# 03_-_MAIN_BOARD.net
KiCad netlist of a schematic drawn in Altium Designer
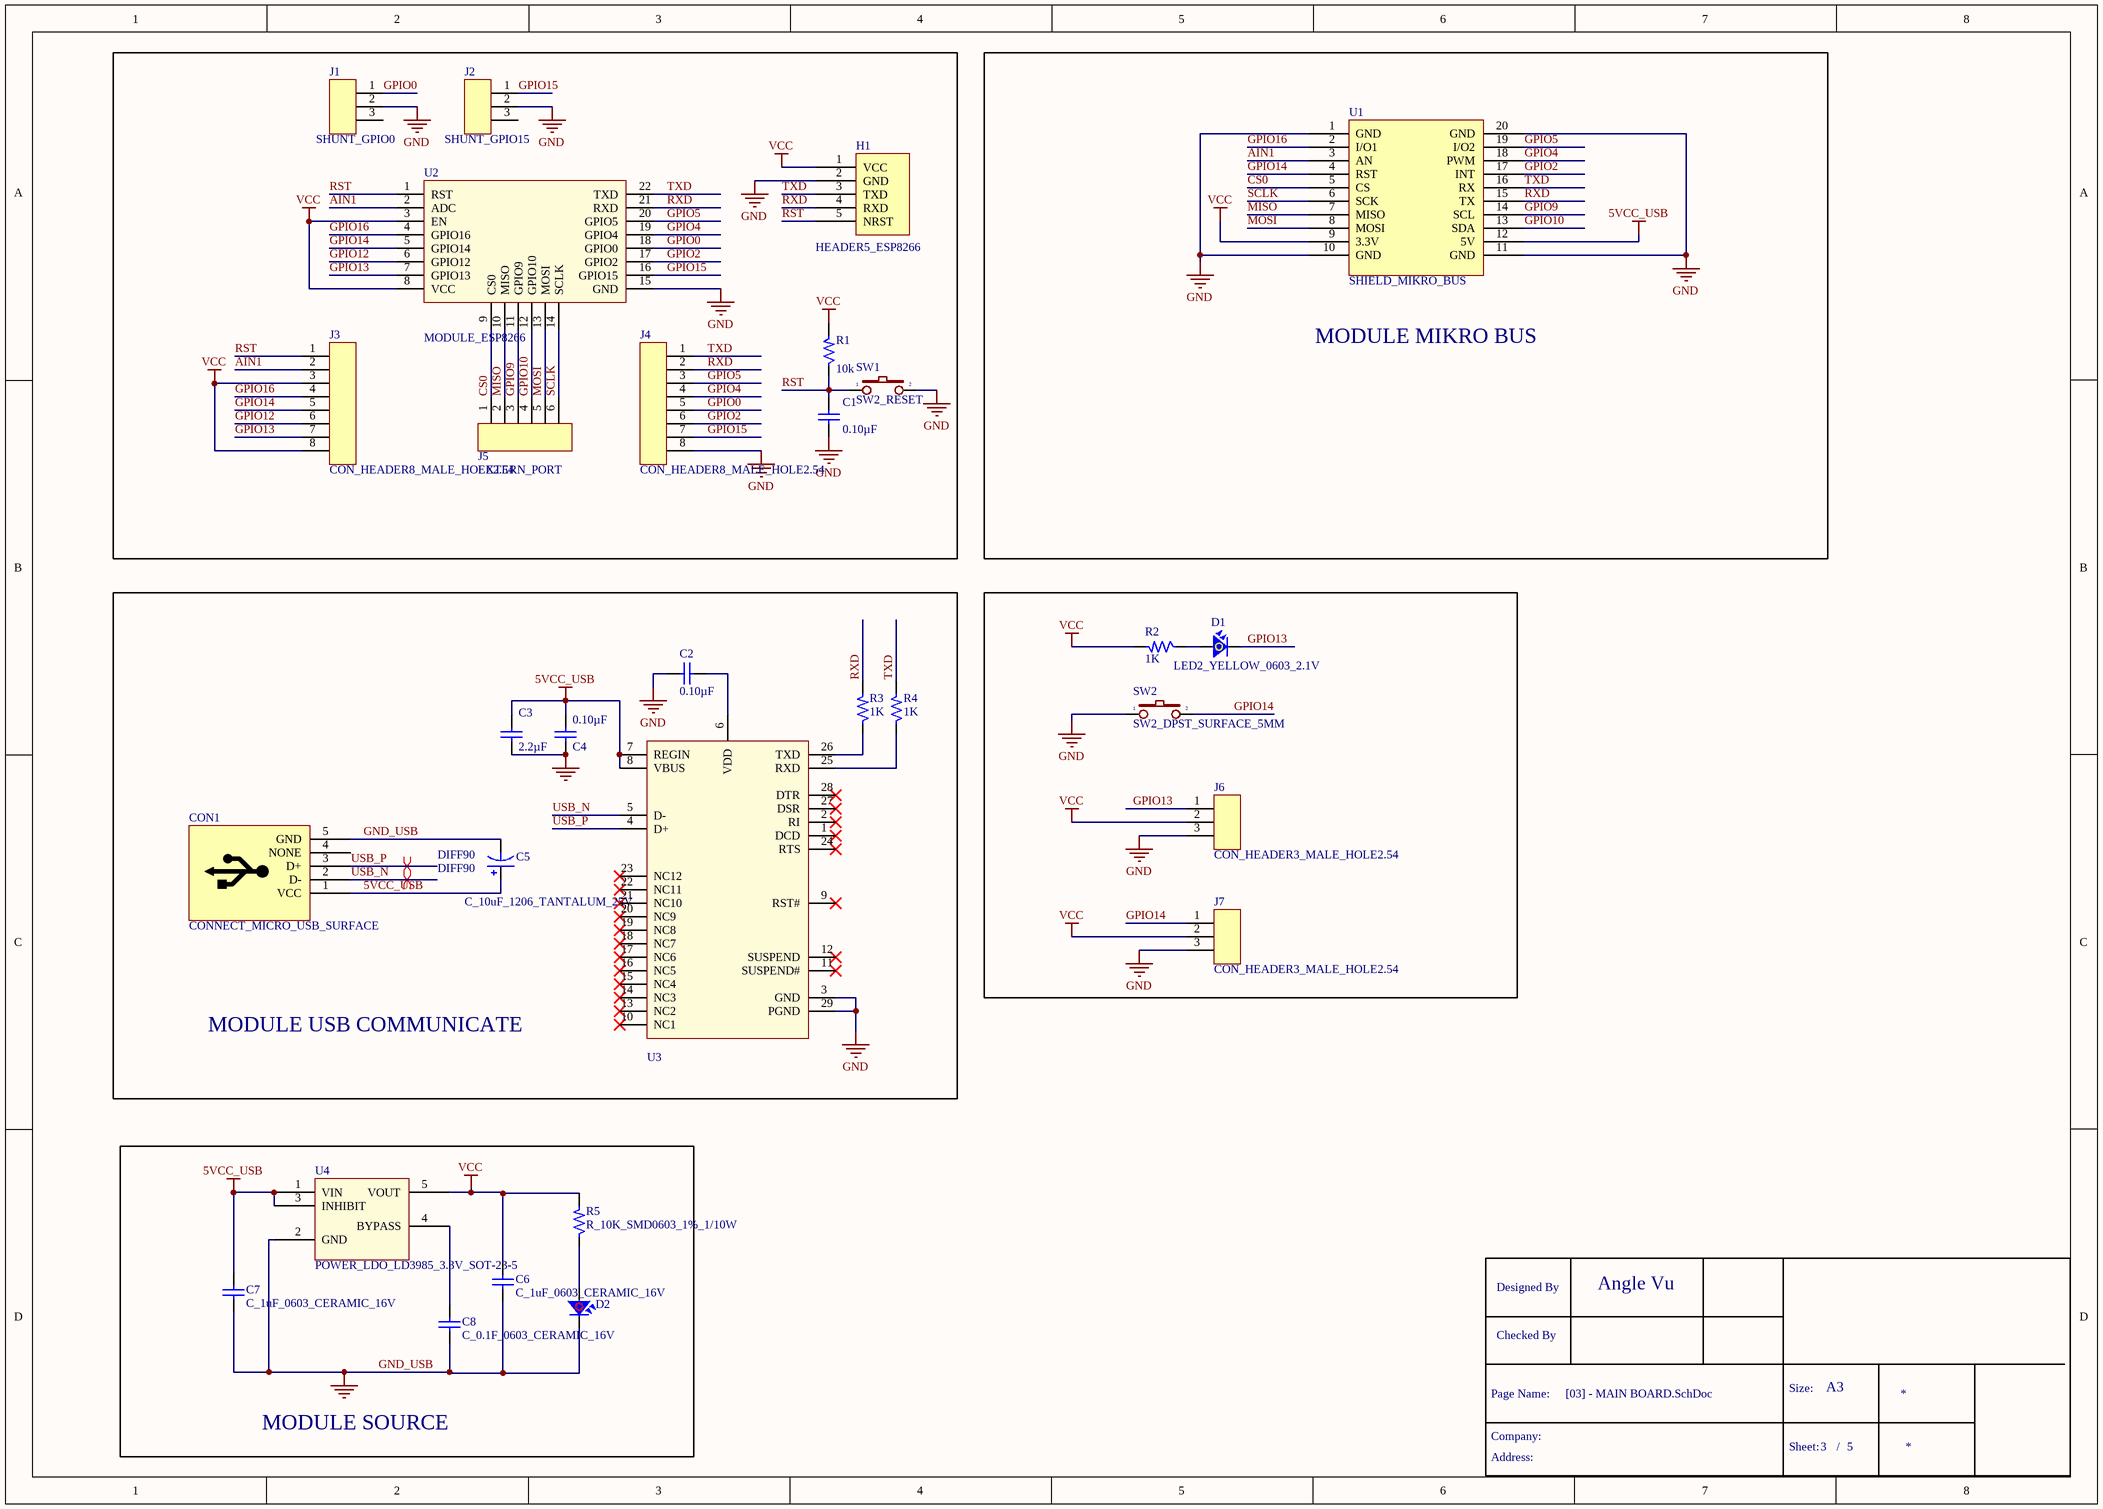
[diagram p0: [03] - MAIN BOARD.SchDoc]

(export (version "E")
  (design (tool "Eeschema 10.0.6"))
  (components
    (comp (ref "C1")
      (value "C_0.1F_0603_CERAMIC_16V")
      (footprint "CAP_SMD0603")
      (description "CAP CER 0.1UF 16V X7R 0603")
      (fields
        (field (name "MANUFACTURER") "Murata Electronics North America")
        (field (name "MANUFACTURER PART NUMBER") "GRM188R71C104KA01D")
        (field (name "CAPACITANCE") "0.10µF")
      )
      (libsource (lib "LIB_ALTIUM") (part "C_0.1F_0603_CERAMIC_16V"))
    )
    (comp (ref "C2")
      (value "C_0.1F_0603_CERAMIC_16V")
      (footprint "CAP_SMD0603")
      (description "CAP CER 0.1UF 16V X7R 0603")
      (fields
        (field (name "MANUFACTURER") "Murata Electronics North America")
        (field (name "MANUFACTURER PART NUMBER") "GRM188R71C104KA01D")
        (field (name "CAPACITANCE") "0.10µF")
      )
      (libsource (lib "LIB_ALTIUM") (part "C_0.1F_0603_CERAMIC_16V"))
    )
    (comp (ref "C3")
      (value "C_2.2uF_0603_CERAMIC_16V")
      (footprint "CAP_SMD0603")
      (description "CAP CER 2.2UF 16V X5R 0603")
      (fields
        (field (name "MANUFACTURER") "Murata Electronics North America")
        (field (name "MANUFACTURER PART NUMBER") "GRM188R61C225KE15D")
        (field (name "CAPACITANCE") "2.2µF")
      )
      (libsource (lib "LIB_ALTIUM") (part "C_2.2uF_0603_CERAMIC_16V"))
    )
    (comp (ref "C4")
      (value "C_0.1F_0603_CERAMIC_16V")
      (footprint "CAP_SMD0603")
      (description "CAP CER 0.1UF 16V X7R 0603")
      (fields
        (field (name "MANUFACTURER") "Murata Electronics North America")
        (field (name "MANUFACTURER PART NUMBER") "GRM188R71C104KA01D")
        (field (name "CAPACITANCE") "0.10µF")
      )
      (libsource (lib "LIB_ALTIUM") (part "C_0.1F_0603_CERAMIC_16V"))
    )
    (comp (ref "C5")
      (value "C_10uF_1206_TANTALUM_25V")
      (footprint "CAP_SMD1206_TANTALUM")
      (description "CAP TANT 10UF 25V 10% 1206")
      (fields
        (field (name "MANUFACTURER") "AVX Corporation")
        (field (name "MANUFACTURER PART NUMBER") "F951E106KAAAQ2")
      )
      (libsource (lib "LIB_ALTIUM") (part "C_10uF_1206_TANTALUM_25V"))
    )
    (comp (ref "C6")
      (value "C_1uF_0603_CERAMIC_16V")
      (footprint "CAP_SMD0603")
      (description "CAP CER 1UF 16V X5R 0603")
      (fields
        (field (name "MANUFACTURER") "Murata Electronics North America")
        (field (name "MANUFACTURER PART NUMBER") "GRM188R61C105KA93D")
      )
      (libsource (lib "LIB_ALTIUM") (part "C_1uF_0603_CERAMIC_16V"))
    )
    (comp (ref "C7")
      (value "C_1uF_0603_CERAMIC_16V")
      (footprint "CAP_SMD0603")
      (description "CAP CER 1UF 16V X5R 0603")
      (fields
        (field (name "MANUFACTURER") "Murata Electronics North America")
        (field (name "MANUFACTURER PART NUMBER") "GRM188R61C105KA93D")
      )
      (libsource (lib "LIB_ALTIUM") (part "C_1uF_0603_CERAMIC_16V"))
    )
    (comp (ref "C8")
      (value "C_0.1F_0603_CERAMIC_16V")
      (footprint "CAP_SMD0603")
      (description "CAP CER 0.1UF 16V X7R 0603")
      (fields
        (field (name "MANUFACTURER") "Murata Electronics North America")
        (field (name "MANUFACTURER PART NUMBER") "GRM188R71C104KA01D")
      )
      (libsource (lib "LIB_ALTIUM") (part "C_0.1F_0603_CERAMIC_16V"))
    )
    (comp (ref "CON1")
      (value "CONNECT_MICRO_USB_SURFACE")
      (footprint "CON_MICRO_USB_HOLE")
      (description "CONN RCPT STD MICRO USB TYPE B")
      (fields
        (field (name "MANUFACTURER") "Amphenol FCI")
        (field (name "MANUFACTURER PART NUMBER") "10103593-0001LF")
      )
      (libsource (lib "LIB_ALTIUM") (part "CONNECT_MICRO_USB_SURFACE"))
    )
    (comp (ref "D1")
      (value "LED2_YELLOW_0603_2.1V")
      (footprint "LED_YELLOW_SMD0603")
      (description "LED YELLOW CLEAR 0603 SMD")
      (fields
        (field (name "MANUFACTURER") "Lite-On Inc.")
        (field (name "MANUFACTURER PART NUMBER") "LTST-C191KSKT")
      )
      (libsource (lib "LIB_ALTIUM") (part "LED2_YELLOW_0603_2.1V"))
    )
    (comp (ref "D2")
      (value "LED2_RED_0603_2V")
      (footprint "LED_RED_SMD0603")
      (description "LED RED CLEAR 0603 SMD")
      (fields
        (field (name "MANUFACTURER") "Lite-On Inc.")
        (field (name "MANUFACTURER PART NUMBER") "LTST-C191KRKT")
      )
      (libsource (lib "LIB_ALTIUM") (part "LED2_RED_0603_2V"))
    )
    (comp (ref "H1")
      (value "HEADER5_ESP8266")
      (footprint "HEADER5_ESP8266_HOLE_2.54")
      (description "CONN HEADER 5 POS 2.54")
      (fields
        (field (name "MANUFACTURER") "Wurth Electronics Inc")
        (field (name "MANUFACTURER PART NUMBER") "61300511121")
      )
      (libsource (lib "LIB_ALTIUM") (part "HEADER5_ESP8266_HOLE_2.54"))
    )
    (comp (ref "J1")
      (value "SHUNT_GPIO0")
      (footprint "CON_HEADER3_HOLE_2.54")
      (description "CON_HEADER10_HOLE2.54")
      (fields (field (name "MANUFACTURER") "3M") (field (name "MANUFACTURER PART NUMBER") "961102-6404-AR"))
      (libsource (lib "") (part "CON_HEADER3_MALE_HOLE2.54_1"))
    )
    (comp (ref "J2")
      (value "SHUNT_GPIO15")
      (footprint "CON_HEADER3_HOLE_2.54")
      (description "CON_HEADER10_HOLE2.54")
      (fields (field (name "MANUFACTURER") "3M") (field (name "MANUFACTURER PART NUMBER") "961102-6404-AR"))
      (libsource (lib "") (part "CON_HEADER3_MALE_HOLE2.54_1"))
    )
    (comp (ref "J3")
      (value "CON_HEADER8_MALE_HOLE2.54")
      (footprint "CON_HEADER8_HOLE_2.54")
      (description "CON_HEADER10_HOLE2.54")
      (fields (field (name "MANUFACTURER") "3M") (field (name "MANUFACTURER PART NUMBER") "961102-6404-AR"))
      (libsource (lib "LIB_ALTIUM") (part "CON_HEADER8_MALE_HOLE2.54"))
    )
    (comp (ref "J4")
      (value "CON_HEADER8_MALE_HOLE2.54")
      (footprint "CON_HEADER8_HOLE_2.54")
      (description "CON_HEADER10_HOLE2.54")
      (fields (field (name "MANUFACTURER") "3M") (field (name "MANUFACTURER PART NUMBER") "961102-6404-AR"))
      (libsource (lib "") (part "CON_HEADER8_MALE_HOLE2.54_1"))
    )
    (comp (ref "J5")
      (value "EXTERN_PORT")
      (footprint "CON_HEADER6_HOLE_2.54")
      (description "CON_HEADER10_HOLE2.54")
      (fields (field (name "MANUFACTURER") "3M") (field (name "MANUFACTURER PART NUMBER") "961102-6404-AR"))
      (libsource (lib "LIB_ALTIUM") (part "CON_HEADER6_MALE_HOLE2.54"))
    )
    (comp (ref "J6")
      (value "CON_HEADER3_MALE_HOLE2.54")
      (footprint "CON_HEADER3_HOLE_2.54")
      (description "CON_HEADER10_HOLE2.54")
      (fields (field (name "MANUFACTURER") "3M") (field (name "MANUFACTURER PART NUMBER") "961102-6404-AR"))
      (libsource (lib "LIB_ALTIUM") (part "CON_HEADER3_MALE_HOLE2.54"))
    )
    (comp (ref "J7")
      (value "CON_HEADER3_MALE_HOLE2.54")
      (footprint "CON_HEADER3_HOLE_2.54")
      (description "CON_HEADER10_HOLE2.54")
      (fields (field (name "MANUFACTURER") "3M") (field (name "MANUFACTURER PART NUMBER") "961102-6404-AR"))
      (libsource (lib "LIB_ALTIUM") (part "CON_HEADER3_MALE_HOLE2.54"))
    )
    (comp (ref "R1")
      (value "R_10K_SMD0603_1%_1/10W")
      (footprint "RES_SMD0603")
      (description "RES SMD 10K OHM 1% 1/10W 0603")
      (fields
        (field (name "MANUFACTURER") "Yageo")
        (field (name "MANUFACTURER PART NUMBER") "RC0603FR-0710KL")
        (field (name "RESISTANCE (OHMS)") "10k")
      )
      (libsource (lib "LIB_ALTIUM") (part "R_10K_SMD0603_1%_1/10W"))
    )
    (comp (ref "R2")
      (value "R_1K2_SMD0603_1%_1/10W")
      (footprint "RES_SMD0603")
      (description "RES SMD 1.2K OHM 1% 1/10W 0603")
      (fields
        (field (name "MANUFACTURER") "Yageo")
        (field (name "MANUFACTURER PART NUMBER") "RC0603FR-071K2L")
        (field (name "RESISTANCE (OHMS)") "1K")
      )
      (libsource (lib "LIB_ALTIUM") (part "R_1K2_SMD0603_1%_1/10W"))
    )
    (comp (ref "R3")
      (value "R_1K2_SMD0603_1%_1/10W")
      (footprint "RES_SMD0603")
      (description "RES SMD 1.2K OHM 1% 1/10W 0603")
      (fields
        (field (name "MANUFACTURER") "Yageo")
        (field (name "MANUFACTURER PART NUMBER") "RC0603FR-071K2L")
        (field (name "RESISTANCE (OHMS)") "1K")
      )
      (libsource (lib "LIB_ALTIUM") (part "R_1K2_SMD0603_1%_1/10W"))
    )
    (comp (ref "R4")
      (value "R_1K2_SMD0603_1%_1/10W")
      (footprint "RES_SMD0603")
      (description "RES SMD 1.2K OHM 1% 1/10W 0603")
      (fields
        (field (name "MANUFACTURER") "Yageo")
        (field (name "MANUFACTURER PART NUMBER") "RC0603FR-071K2L")
        (field (name "RESISTANCE (OHMS)") "1K")
      )
      (libsource (lib "LIB_ALTIUM") (part "R_1K2_SMD0603_1%_1/10W"))
    )
    (comp (ref "R5")
      (value "R_10K_SMD0603_1%_1/10W")
      (footprint "RES_SMD0603")
      (description "RES SMD 10K OHM 1% 1/10W 0603")
      (fields
        (field (name "MANUFACTURER") "Yageo")
        (field (name "MANUFACTURER PART NUMBER") "RC0603FR-0710KL")
      )
      (libsource (lib "LIB_ALTIUM") (part "R_10K_SMD0603_1%_1/10W"))
    )
    (comp (ref "SW1")
      (value "SW2_RESET")
      (footprint "SW2-SMD")
      (description "SWITCH TACTILE SPST-NO 0.05A 12V")
      (fields
        (field (name "MANUFACTURER") "Wurth Electronics Inc")
        (field (name "MANUFACTURER PART NUMBER") "434121050836")
      )
      (libsource (lib "LIB_ALTIUM") (part "SW2_DPST_SURFACE_5MM"))
    )
    (comp (ref "SW2")
      (value "SW2_DPST_SURFACE_5MM")
      (footprint "SW2-SMD")
      (description "SWITCH TACTILE SPST-NO 0.05A 12V")
      (fields
        (field (name "MANUFACTURER") "Wurth Electronics Inc")
        (field (name "MANUFACTURER PART NUMBER") "434121050836")
      )
      (libsource (lib "LIB_ALTIUM") (part "SW2_DPST_SURFACE_5MM"))
    )
    (comp (ref "U1")
      (value "SHIELD_MIKRO_BUS")
      (footprint "SHIELD_MIKRO_BUS")
      (libsource (lib "SchematicLib") (part "SHIELD_MIKRO_BUS"))
    )
    (comp (ref "U2")
      (value "MODULE_ESP8266")
      (footprint "MODULE_ESP8266")
      (libsource (lib "LIB_ALTIUM") (part "MODULE_ESP8266"))
    )
    (comp (ref "U3")
      (value "USB_CP2102-GMR")
      (footprint "QFN_28PIN_USBC2102")
      (description "IC USB-TO-UART BRIDGE 28VQFN")
      (fields
        (field (name "MANUFACTURER") "Silicon Labs")
        (field (name "MANUFACTURER PART NUMBER") "CP2102-GMR")
      )
      (libsource (lib "LIB_ALTIUM") (part "USB_CP2102-GMR"))
    )
    (comp (ref "U4")
      (value "POWER_LDO_LD3985_3.3V_SOT-23-5")
      (footprint "POWER_LDO_LDR3985-3.3")
      (description "IC REG LDO 3.3V 0.15A SOT23-5")
      (fields
        (field (name "MANUFACTURER") "STMicroelectronics")
        (field (name "MANUFACTURER PART NUMBER") "LD3985M33R")
      )
      (libsource (lib "LIB_ALTIUM") (part "POWER_LDO_LD3985_3.3V_SOT-23-5"))
    )
  )
  (nets
    (net (code "1") (name "/AIN1") (class "Default")
      (node (ref "J3") (pin "2") (pinfunction "SIGN-_2") (pintype "passive"))
      (node (ref "U1") (pin "3") (pinfunction "AN_3") (pintype "passive"))
      (node (ref "U2") (pin "2") (pinfunction "ADC_2") (pintype "passive"))
    )
    (net (code "2") (name "/CS0") (class "Default")
      (node (ref "J5") (pin "1") (pinfunction "SIGN+_1") (pintype "passive"))
      (node (ref "U1") (pin "5") (pinfunction "CS_5") (pintype "passive"))
      (node (ref "U2") (pin "9") (pinfunction "CS0_9") (pintype "passive"))
    )
    (net (code "3") (name "/GPIO0") (class "Default")
      (node (ref "J1") (pin "1") (pinfunction "SIGN+_1") (pintype "passive"))
      (node (ref "J4") (pin "5") (pinfunction "5_5") (pintype "passive"))
      (node (ref "U2") (pin "18") (pinfunction "GPIO0_18") (pintype "passive"))
    )
    (net (code "4") (name "/GPIO2") (class "Default")
      (node (ref "J4") (pin "6") (pinfunction "6_6") (pintype "passive"))
      (node (ref "U1") (pin "17") (pinfunction "INT_17") (pintype "passive"))
      (node (ref "U2") (pin "17") (pinfunction "GPIO2_17") (pintype "passive"))
    )
    (net (code "5") (name "/GPIO4") (class "Default")
      (node (ref "J4") (pin "4") (pinfunction "4_4") (pintype "passive"))
      (node (ref "U1") (pin "18") (pinfunction "PWM_18") (pintype "passive"))
      (node (ref "U2") (pin "19") (pinfunction "GPIO4_19") (pintype "passive"))
    )
    (net (code "6") (name "/GPIO5") (class "Default")
      (node (ref "J4") (pin "3") (pinfunction "3_3") (pintype "passive"))
      (node (ref "U1") (pin "19") (pinfunction "I/O2_19") (pintype "passive"))
      (node (ref "U2") (pin "20") (pinfunction "GPIO5_20") (pintype "passive"))
    )
    (net (code "7") (name "/GPIO9") (class "Default")
      (node (ref "J5") (pin "3") (pinfunction "3_3") (pintype "passive"))
      (node (ref "U1") (pin "14") (pinfunction "SCL_14") (pintype "passive"))
      (node (ref "U2") (pin "11") (pinfunction "GPIO9_11") (pintype "passive"))
    )
    (net (code "8") (name "/GPIO10") (class "Default")
      (node (ref "J5") (pin "4") (pinfunction "4_4") (pintype "passive"))
      (node (ref "U1") (pin "13") (pinfunction "SDA_13") (pintype "passive"))
      (node (ref "U2") (pin "12") (pinfunction "GPIO10_12") (pintype "passive"))
    )
    (net (code "9") (name "/GPIO12") (class "Default")
      (node (ref "J3") (pin "6") (pinfunction "6_6") (pintype "passive"))
      (node (ref "U2") (pin "6") (pinfunction "GPIO12_6") (pintype "passive"))
    )
    (net (code "10") (name "/GPIO13") (class "Default")
      (node (ref "D1") (pin "2") (pinfunction "2_2") (pintype "passive"))
      (node (ref "J3") (pin "7") (pinfunction "7_7") (pintype "passive"))
      (node (ref "J6") (pin "1") (pinfunction "SIGN+_1") (pintype "passive"))
      (node (ref "U2") (pin "7") (pinfunction "GPIO13_7") (pintype "passive"))
    )
    (net (code "11") (name "/GPIO14") (class "Default")
      (node (ref "J3") (pin "5") (pinfunction "5_5") (pintype "passive"))
      (node (ref "J7") (pin "1") (pinfunction "SIGN+_1") (pintype "passive"))
      (node (ref "SW2") (pin "2") (pinfunction "2_2") (pintype "passive"))
      (node (ref "U1") (pin "4") (pinfunction "RST_4") (pintype "passive"))
      (node (ref "U2") (pin "5") (pinfunction "GPIO14_5") (pintype "passive"))
    )
    (net (code "12") (name "/GPIO15") (class "Default")
      (node (ref "J2") (pin "1") (pinfunction "SIGN+_1") (pintype "passive"))
      (node (ref "J4") (pin "7") (pinfunction "7_7") (pintype "passive"))
      (node (ref "U2") (pin "16") (pinfunction "GPIO15_16") (pintype "passive"))
    )
    (net (code "13") (name "/GPIO16") (class "Default")
      (node (ref "J3") (pin "4") (pinfunction "4_4") (pintype "passive"))
      (node (ref "U1") (pin "2") (pinfunction "I/O1_2") (pintype "passive"))
      (node (ref "U2") (pin "4") (pinfunction "GPIO16_4") (pintype "passive"))
    )
    (net (code "14") (name "/MISO") (class "Default")
      (node (ref "J5") (pin "2") (pinfunction "SIGN-_2") (pintype "passive"))
      (node (ref "U1") (pin "7") (pinfunction "MISO_7") (pintype "passive"))
      (node (ref "U2") (pin "10") (pinfunction "MISO_10") (pintype "passive"))
    )
    (net (code "15") (name "/MOSI") (class "Default")
      (node (ref "J5") (pin "5") (pinfunction "5_5") (pintype "passive"))
      (node (ref "U1") (pin "8") (pinfunction "MOSI_8") (pintype "passive"))
      (node (ref "U2") (pin "13") (pinfunction "MOSI_13") (pintype "passive"))
    )
    (net (code "16") (name "/RST") (class "Default")
      (node (ref "C1") (pin "2") (pinfunction "2_2") (pintype "passive"))
      (node (ref "H1") (pin "5") (pinfunction "NRST_5") (pintype "passive"))
      (node (ref "J3") (pin "1") (pinfunction "SIGN+_1") (pintype "passive"))
      (node (ref "R1") (pin "1") (pinfunction "1_1") (pintype "passive"))
      (node (ref "SW1") (pin "1") (pinfunction "1_1") (pintype "passive"))
      (node (ref "U2") (pin "1") (pinfunction "RST_1") (pintype "passive"))
    )
    (net (code "17") (name "/RXD") (class "Default")
      (node (ref "H1") (pin "4") (pinfunction "RXD_4") (pintype "passive"))
      (node (ref "J4") (pin "2") (pinfunction "SIGN-_2") (pintype "passive"))
      (node (ref "R3") (pin "2") (pinfunction "2_2") (pintype "passive"))
      (node (ref "U1") (pin "15") (pinfunction "TX_15") (pintype "passive"))
      (node (ref "U2") (pin "21") (pinfunction "RXD_21") (pintype "passive"))
    )
    (net (code "18") (name "/SCLK") (class "Default")
      (node (ref "J5") (pin "6") (pinfunction "6_6") (pintype "passive"))
      (node (ref "U1") (pin "6") (pinfunction "SCK_6") (pintype "passive"))
      (node (ref "U2") (pin "14") (pinfunction "SCLK_14") (pintype "passive"))
    )
    (net (code "19") (name "/TXD") (class "Default")
      (node (ref "H1") (pin "3") (pinfunction "TXD_3") (pintype "passive"))
      (node (ref "J4") (pin "1") (pinfunction "SIGN+_1") (pintype "passive"))
      (node (ref "R4") (pin "2") (pinfunction "2_2") (pintype "passive"))
      (node (ref "U1") (pin "16") (pinfunction "RX_16") (pintype "passive"))
      (node (ref "U2") (pin "22") (pinfunction "TXD_22") (pintype "passive"))
    )
    (net (code "20") (name "/USB_N") (class "Default")
      (node (ref "CON1") (pin "2") (pinfunction "D-_2") (pintype "passive"))
      (node (ref "U3") (pin "5") (pinfunction "D-_5") (pintype "passive"))
    )
    (net (code "21") (name "/USB_P") (class "Default")
      (node (ref "CON1") (pin "3") (pinfunction "D+_3") (pintype "passive"))
      (node (ref "U3") (pin "4") (pinfunction "D+_4") (pintype "passive"))
    )
    (net (code "22") (name "5VCC_USB") (class "Default")
      (node (ref "C3") (pin "2") (pinfunction "2_2") (pintype "passive"))
      (node (ref "C4") (pin "2") (pinfunction "2_2") (pintype "passive"))
      (node (ref "C5") (pin "1") (pinfunction "1_1") (pintype "passive"))
      (node (ref "C7") (pin "2") (pinfunction "2_2") (pintype "passive"))
      (node (ref "CON1") (pin "1") (pinfunction "VCC_1") (pintype "passive"))
      (node (ref "U1") (pin "12") (pinfunction "5V_12") (pintype "passive"))
      (node (ref "U3") (pin "7") (pinfunction "REGIN_7") (pintype "passive"))
      (node (ref "U3") (pin "8") (pinfunction "VBUS_8") (pintype "passive"))
      (node (ref "U4") (pin "1") (pinfunction "VIN_1") (pintype "passive"))
      (node (ref "U4") (pin "3") (pinfunction "INHIBIT_3") (pintype "passive"))
    )
    (net (code "23") (name "GND") (class "Default")
      (node (ref "C1") (pin "1") (pinfunction "1_1") (pintype "passive"))
      (node (ref "C2") (pin "2") (pinfunction "2_2") (pintype "passive"))
      (node (ref "C3") (pin "1") (pinfunction "1_1") (pintype "passive"))
      (node (ref "C4") (pin "1") (pinfunction "1_1") (pintype "passive"))
      (node (ref "C5") (pin "2") (pinfunction "2_2") (pintype "passive"))
      (node (ref "C6") (pin "1") (pinfunction "1_1") (pintype "passive"))
      (node (ref "C7") (pin "1") (pinfunction "1_1") (pintype "passive"))
      (node (ref "C8") (pin "1") (pinfunction "1_1") (pintype "passive"))
      (node (ref "CON1") (pin "5") (pinfunction "GND_5") (pintype "passive"))
      (node (ref "D2") (pin "2") (pinfunction "2_2") (pintype "passive"))
      (node (ref "H1") (pin "2") (pinfunction "GND_2") (pintype "passive"))
      (node (ref "J1") (pin "2") (pinfunction "SIGN-_2") (pintype "passive"))
      (node (ref "J2") (pin "2") (pinfunction "SIGN-_2") (pintype "passive"))
      (node (ref "J4") (pin "8") (pinfunction "8_8") (pintype "passive"))
      (node (ref "J6") (pin "3") (pinfunction "3_3") (pintype "passive"))
      (node (ref "J7") (pin "3") (pinfunction "3_3") (pintype "passive"))
      (node (ref "SW1") (pin "2") (pinfunction "2_2") (pintype "passive"))
      (node (ref "SW2") (pin "1") (pinfunction "1_1") (pintype "passive"))
      (node (ref "U1") (pin "1") (pinfunction "GND_1") (pintype "passive"))
      (node (ref "U1") (pin "10") (pinfunction "GND_10") (pintype "passive"))
      (node (ref "U1") (pin "11") (pinfunction "GND_11") (pintype "passive"))
      (node (ref "U1") (pin "20") (pinfunction "GND_20") (pintype "passive"))
      (node (ref "U2") (pin "15") (pinfunction "GND_15") (pintype "passive"))
      (node (ref "U3") (pin "29") (pinfunction "PGND_29") (pintype "passive"))
      (node (ref "U3") (pin "3") (pinfunction "GND_3") (pintype "passive"))
      (node (ref "U4") (pin "2") (pinfunction "GND_2") (pintype "passive"))
    )
    (net (code "24") (name "Net-(D1-Pad1)") (class "Default")
      (node (ref "D1") (pin "1") (pinfunction "1_1") (pintype "passive"))
      (node (ref "R2") (pin "1") (pinfunction "1_1") (pintype "passive"))
    )
    (net (code "25") (name "Net-(D2-Pad1)") (class "Default")
      (node (ref "D2") (pin "1") (pinfunction "1_1") (pintype "passive"))
      (node (ref "R5") (pin "1") (pinfunction "1_1") (pintype "passive"))
    )
    (net (code "26") (name "Net-(U3-RXD)") (class "Default")
      (node (ref "R4") (pin "1") (pinfunction "1_1") (pintype "passive"))
      (node (ref "U3") (pin "25") (pinfunction "RXD_25") (pintype "passive"))
    )
    (net (code "27") (name "Net-(U3-TXD)") (class "Default")
      (node (ref "R3") (pin "1") (pinfunction "1_1") (pintype "passive"))
      (node (ref "U3") (pin "26") (pinfunction "TXD_26") (pintype "passive"))
    )
    (net (code "28") (name "Net-(U3-VDD)") (class "Default")
      (node (ref "C2") (pin "1") (pinfunction "1_1") (pintype "passive"))
      (node (ref "U3") (pin "6") (pinfunction "VDD_6") (pintype "passive"))
    )
    (net (code "29") (name "Net-(U4-BYPASS)") (class "Default")
      (node (ref "C8") (pin "2") (pinfunction "2_2") (pintype "passive"))
      (node (ref "U4") (pin "4") (pinfunction "BYPASS_4") (pintype "passive"))
    )
    (net (code "30") (name "VCC") (class "Default")
      (node (ref "C6") (pin "2") (pinfunction "2_2") (pintype "passive"))
      (node (ref "H1") (pin "1") (pinfunction "VCC_1") (pintype "passive"))
      (node (ref "J3") (pin "3") (pinfunction "3_3") (pintype "passive"))
      (node (ref "J3") (pin "8") (pinfunction "8_8") (pintype "passive"))
      (node (ref "J6") (pin "2") (pinfunction "SIGN-_2") (pintype "passive"))
      (node (ref "J7") (pin "2") (pinfunction "SIGN-_2") (pintype "passive"))
      (node (ref "R1") (pin "2") (pinfunction "2_2") (pintype "passive"))
      (node (ref "R2") (pin "2") (pinfunction "2_2") (pintype "passive"))
      (node (ref "R5") (pin "2") (pinfunction "2_2") (pintype "passive"))
      (node (ref "U1") (pin "9") (pinfunction "3.3V_9") (pintype "passive"))
      (node (ref "U2") (pin "3") (pinfunction "EN_3") (pintype "passive"))
      (node (ref "U2") (pin "8") (pinfunction "VCC_8") (pintype "passive"))
      (node (ref "U4") (pin "5") (pinfunction "VOUT_5") (pintype "passive"))
    )
    (net (code "31") (name "unconnected-(CON1-NONE-Pad4)") (class "Default")
      (node (ref "CON1") (pin "4") (pinfunction "NONE_4") (pintype "passive"))
    )
    (net (code "32") (name "unconnected-(J1-Pad3)") (class "Default")
      (node (ref "J1") (pin "3") (pinfunction "3_3") (pintype "passive"))
    )
    (net (code "33") (name "unconnected-(J2-Pad3)") (class "Default")
      (node (ref "J2") (pin "3") (pinfunction "3_3") (pintype "passive"))
    )
    (net (code "34") (name "unconnected-(U3-DCD-Pad1)") (class "Default")
      (node (ref "U3") (pin "1") (pinfunction "DCD_1") (pintype "passive+no_connect"))
    )
    (net (code "35") (name "unconnected-(U3-DSR-Pad27)") (class "Default")
      (node (ref "U3") (pin "27") (pinfunction "DSR_27") (pintype "passive+no_connect"))
    )
    (net (code "36") (name "unconnected-(U3-DTR-Pad28)") (class "Default")
      (node (ref "U3") (pin "28") (pinfunction "DTR_28") (pintype "passive+no_connect"))
    )
    (net (code "37") (name "unconnected-(U3-NC1-Pad10)") (class "Default")
      (node (ref "U3") (pin "10") (pinfunction "NC1_10") (pintype "passive+no_connect"))
    )
    (net (code "38") (name "unconnected-(U3-NC2-Pad13)") (class "Default")
      (node (ref "U3") (pin "13") (pinfunction "NC2_13") (pintype "passive+no_connect"))
    )
    (net (code "39") (name "unconnected-(U3-NC3-Pad14)") (class "Default")
      (node (ref "U3") (pin "14") (pinfunction "NC3_14") (pintype "passive+no_connect"))
    )
    (net (code "40") (name "unconnected-(U3-NC4-Pad15)") (class "Default")
      (node (ref "U3") (pin "15") (pinfunction "NC4_15") (pintype "passive+no_connect"))
    )
    (net (code "41") (name "unconnected-(U3-NC5-Pad16)") (class "Default")
      (node (ref "U3") (pin "16") (pinfunction "NC5_16") (pintype "passive+no_connect"))
    )
    (net (code "42") (name "unconnected-(U3-NC6-Pad17)") (class "Default")
      (node (ref "U3") (pin "17") (pinfunction "NC6_17") (pintype "passive+no_connect"))
    )
    (net (code "43") (name "unconnected-(U3-NC7-Pad18)") (class "Default")
      (node (ref "U3") (pin "18") (pinfunction "NC7_18") (pintype "passive+no_connect"))
    )
    (net (code "44") (name "unconnected-(U3-NC8-Pad19)") (class "Default")
      (node (ref "U3") (pin "19") (pinfunction "NC8_19") (pintype "passive+no_connect"))
    )
    (net (code "45") (name "unconnected-(U3-NC9-Pad20)") (class "Default")
      (node (ref "U3") (pin "20") (pinfunction "NC9_20") (pintype "passive+no_connect"))
    )
    (net (code "46") (name "unconnected-(U3-NC10-Pad21)") (class "Default")
      (node (ref "U3") (pin "21") (pinfunction "NC10_21") (pintype "passive+no_connect"))
    )
    (net (code "47") (name "unconnected-(U3-NC11-Pad22)") (class "Default")
      (node (ref "U3") (pin "22") (pinfunction "NC11_22") (pintype "passive+no_connect"))
    )
    (net (code "48") (name "unconnected-(U3-NC12-Pad23)") (class "Default")
      (node (ref "U3") (pin "23") (pinfunction "NC12_23") (pintype "passive+no_connect"))
    )
    (net (code "49") (name "unconnected-(U3-RI-Pad2)") (class "Default")
      (node (ref "U3") (pin "2") (pinfunction "RI_2") (pintype "passive+no_connect"))
    )
    (net (code "50") (name "unconnected-(U3-RST#-Pad9)") (class "Default")
      (node (ref "U3") (pin "9") (pinfunction "RST#_9") (pintype "passive+no_connect"))
    )
    (net (code "51") (name "unconnected-(U3-RTS-Pad24)") (class "Default")
      (node (ref "U3") (pin "24") (pinfunction "RTS_24") (pintype "passive+no_connect"))
    )
    (net (code "52") (name "unconnected-(U3-SUSPEND#-Pad11)") (class "Default")
      (node (ref "U3") (pin "11") (pinfunction "SUSPEND#_11") (pintype "passive+no_connect"))
    )
    (net (code "53") (name "unconnected-(U3-SUSPEND-Pad12)") (class "Default")
      (node (ref "U3") (pin "12") (pinfunction "SUSPEND_12") (pintype "passive+no_connect"))
    )
  )
)
